# CAN.net
KiCad netlist of a schematic drawn in Altium Designer
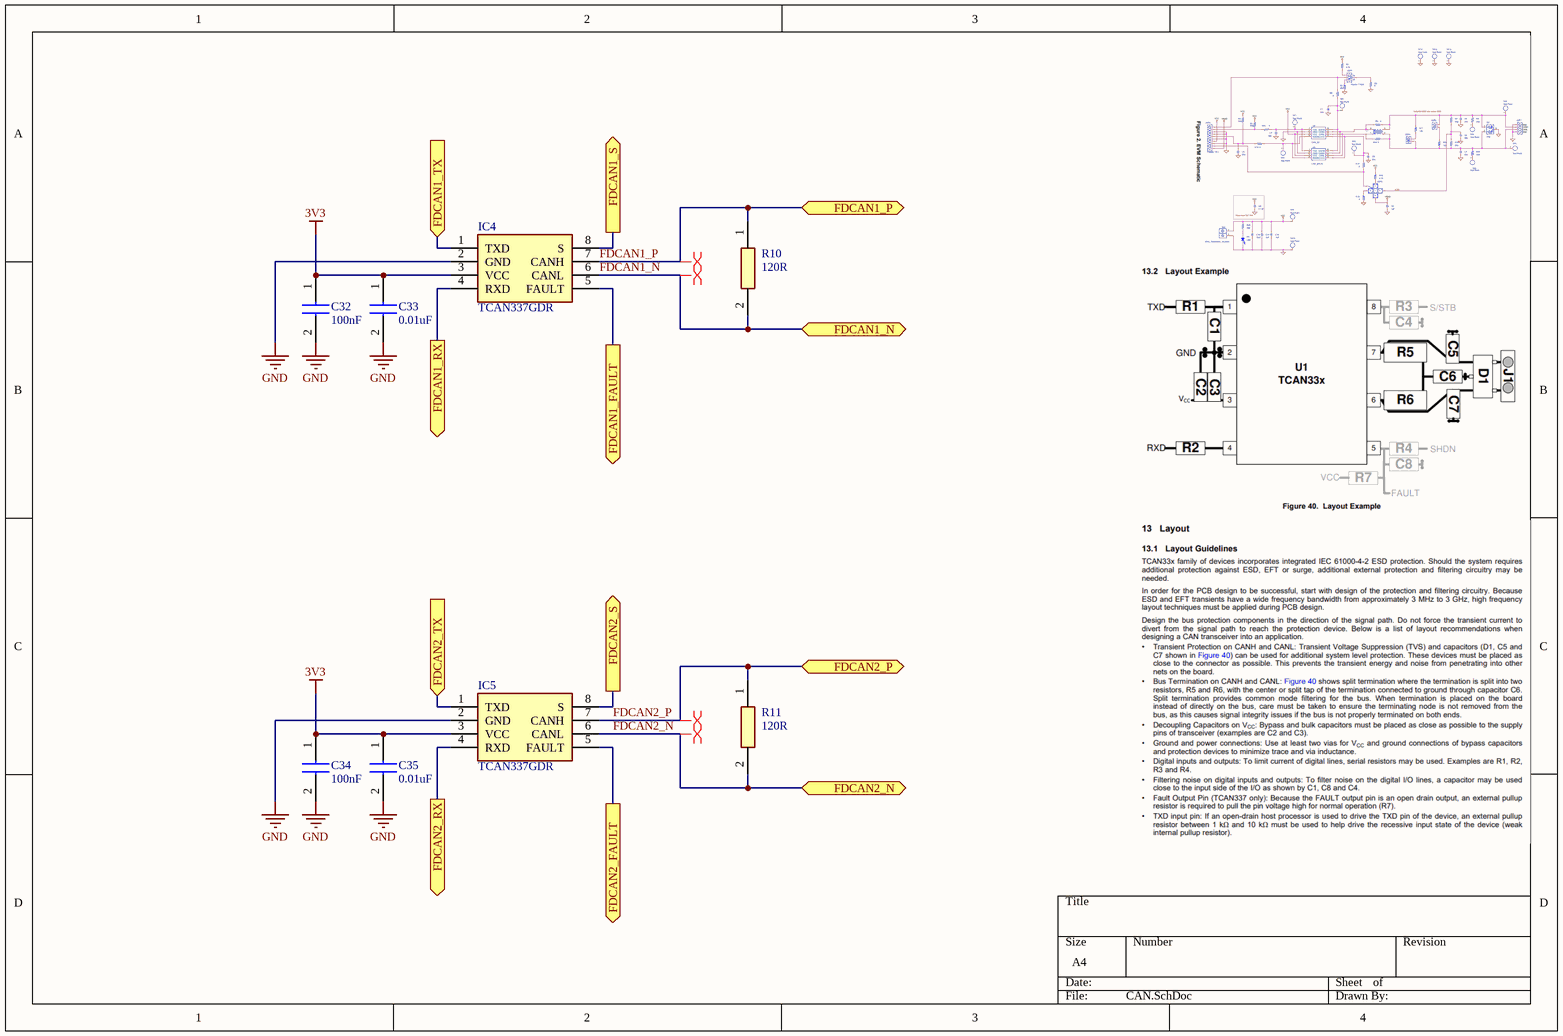
[diagram p0: CAN.SchDoc]

(export (version "E")
  (design (tool "Eeschema 10.0.6"))
  (components
    (comp (ref "C32")
      (value "100nF")
      (footprint "RT_IS:CAPC1608X95N")
      (description "0.1 µF ±20% 16V Ceramic Capacitor X7R 0603 (1608 Metric)")
      (fields (field (name "MANUFACTURER_PART_NUMBER") "C0603C104M4RAC7867"))
      (libsource (lib "*") (part "C0603C104M4RAC7867"))
    )
    (comp (ref "C33")
      (value "0.01uF")
      (footprint "RT_IS:C0603")
      (description "10000 pF ±10% 63V Ceramic Capacitor X7R 0603 (1608 Metric)")
      (fields
        (field (name "MANUFACTURER_PART_NUMBER") "C0603C103KMRECAUTO")
        (field (name "MOUSER PART NUMBER") "80-C0603C103KMREAUTO")
      )
      (libsource (lib "*") (part "C0603C103KMRECAUTO"))
    )
    (comp (ref "C34")
      (value "100nF")
      (footprint "RT_IS:CAPC1608X95N")
      (description "0.1 µF ±20% 16V Ceramic Capacitor X7R 0603 (1608 Metric)")
      (fields (field (name "MANUFACTURER_PART_NUMBER") "C0603C104M4RAC7867"))
      (libsource (lib "*") (part "C0603C104M4RAC7867"))
    )
    (comp (ref "C35")
      (value "0.01uF")
      (footprint "RT_IS:C0603")
      (description "10000 pF ±10% 63V Ceramic Capacitor X7R 0603 (1608 Metric)")
      (fields
        (field (name "MANUFACTURER_PART_NUMBER") "C0603C103KMRECAUTO")
        (field (name "MOUSER PART NUMBER") "80-C0603C103KMREAUTO")
      )
      (libsource (lib "*") (part "C0603C103KMRECAUTO"))
    )
    (comp (ref "IC4")
      (value "TCAN337GDR")
      (footprint "RT_IS:SOIC127P600X175-8N")
      (description "1/1 Transceiver CANbus 8-SOIC")
      (fields (field (name "MOUSER PART NUMBER") "595-TCAN337GDR"))
      (libsource (lib "*") (part "TCAN337GDR"))
    )
    (comp (ref "IC5")
      (value "TCAN337GDR")
      (footprint "RT_IS:SOIC127P600X175-8N")
      (description "1/1 Transceiver CANbus 8-SOIC")
      (fields (field (name "MOUSER PART NUMBER") "595-TCAN337GDR"))
      (libsource (lib "*") (part "TCAN337GDR"))
    )
    (comp (ref "R10")
      (value "120R")
      (footprint "RT_IS:ERA6VK")
      (fields
        (field (name "MANUFACTURER_PART_NUMBER") "ERA-6VEB1200V")
        (field (name "MOUSER PART NUMBER") "667-ERA-6VEB1200V")
      )
      (libsource (lib "*") (part "ERA-6VEB1200V"))
    )
    (comp (ref "R11")
      (value "120R")
      (footprint "RT_IS:ERA6VK")
      (fields
        (field (name "MANUFACTURER_PART_NUMBER") "ERA-6VEB1200V")
        (field (name "MOUSER PART NUMBER") "667-ERA-6VEB1200V")
      )
      (libsource (lib "*") (part "ERA-6VEB1200V"))
    )
  )
  (nets
    (net (code "1") (name "/FDCAN1_FAULT") (class "Default")
      (node (ref "IC4") (pin "5") (pinfunction "FAULT_5") (pintype "passive"))
    )
    (net (code "2") (name "/FDCAN1_N") (class "Default")
      (node (ref "IC4") (pin "6") (pinfunction "CANL_6") (pintype "passive"))
      (node (ref "R10") (pin "2") (pinfunction "2_2") (pintype "passive"))
    )
    (net (code "3") (name "/FDCAN1_P") (class "Default")
      (node (ref "IC4") (pin "7") (pinfunction "CANH_7") (pintype "passive"))
      (node (ref "R10") (pin "1") (pinfunction "1_1") (pintype "passive"))
    )
    (net (code "4") (name "/FDCAN1_RX") (class "Default")
      (node (ref "IC4") (pin "4") (pinfunction "RXD_4") (pintype "passive"))
    )
    (net (code "5") (name "/FDCAN1_S") (class "Default")
      (node (ref "IC4") (pin "8") (pinfunction "S_8") (pintype "passive"))
    )
    (net (code "6") (name "/FDCAN1_TX") (class "Default")
      (node (ref "IC4") (pin "1") (pinfunction "TXD_1") (pintype "passive"))
    )
    (net (code "7") (name "/FDCAN2_FAULT") (class "Default")
      (node (ref "IC5") (pin "5") (pinfunction "FAULT_5") (pintype "passive"))
    )
    (net (code "8") (name "/FDCAN2_N") (class "Default")
      (node (ref "IC5") (pin "6") (pinfunction "CANL_6") (pintype "passive"))
      (node (ref "R11") (pin "2") (pinfunction "2_2") (pintype "passive"))
    )
    (net (code "9") (name "/FDCAN2_P") (class "Default")
      (node (ref "IC5") (pin "7") (pinfunction "CANH_7") (pintype "passive"))
      (node (ref "R11") (pin "1") (pinfunction "1_1") (pintype "passive"))
    )
    (net (code "10") (name "/FDCAN2_RX") (class "Default")
      (node (ref "IC5") (pin "4") (pinfunction "RXD_4") (pintype "passive"))
    )
    (net (code "11") (name "/FDCAN2_S") (class "Default")
      (node (ref "IC5") (pin "8") (pinfunction "S_8") (pintype "passive"))
    )
    (net (code "12") (name "/FDCAN2_TX") (class "Default")
      (node (ref "IC5") (pin "1") (pinfunction "TXD_1") (pintype "passive"))
    )
    (net (code "13") (name "3V3") (class "Default")
      (node (ref "C32") (pin "1") (pinfunction "1_1") (pintype "passive"))
      (node (ref "C33") (pin "1") (pinfunction "1_1") (pintype "passive"))
      (node (ref "C34") (pin "1") (pinfunction "1_1") (pintype "passive"))
      (node (ref "C35") (pin "1") (pinfunction "1_1") (pintype "passive"))
      (node (ref "IC4") (pin "3") (pinfunction "VCC_3") (pintype "passive"))
      (node (ref "IC5") (pin "3") (pinfunction "VCC_3") (pintype "passive"))
    )
    (net (code "14") (name "GND") (class "Default")
      (node (ref "C32") (pin "2") (pinfunction "2_2") (pintype "passive"))
      (node (ref "C33") (pin "2") (pinfunction "2_2") (pintype "passive"))
      (node (ref "C34") (pin "2") (pinfunction "2_2") (pintype "passive"))
      (node (ref "C35") (pin "2") (pinfunction "2_2") (pintype "passive"))
      (node (ref "IC4") (pin "2") (pinfunction "GND_2") (pintype "passive"))
      (node (ref "IC5") (pin "2") (pinfunction "GND_2") (pintype "passive"))
    )
  )
)
